# PG04__BALANCER.net
KiCad netlist of a schematic drawn in Altium Designer
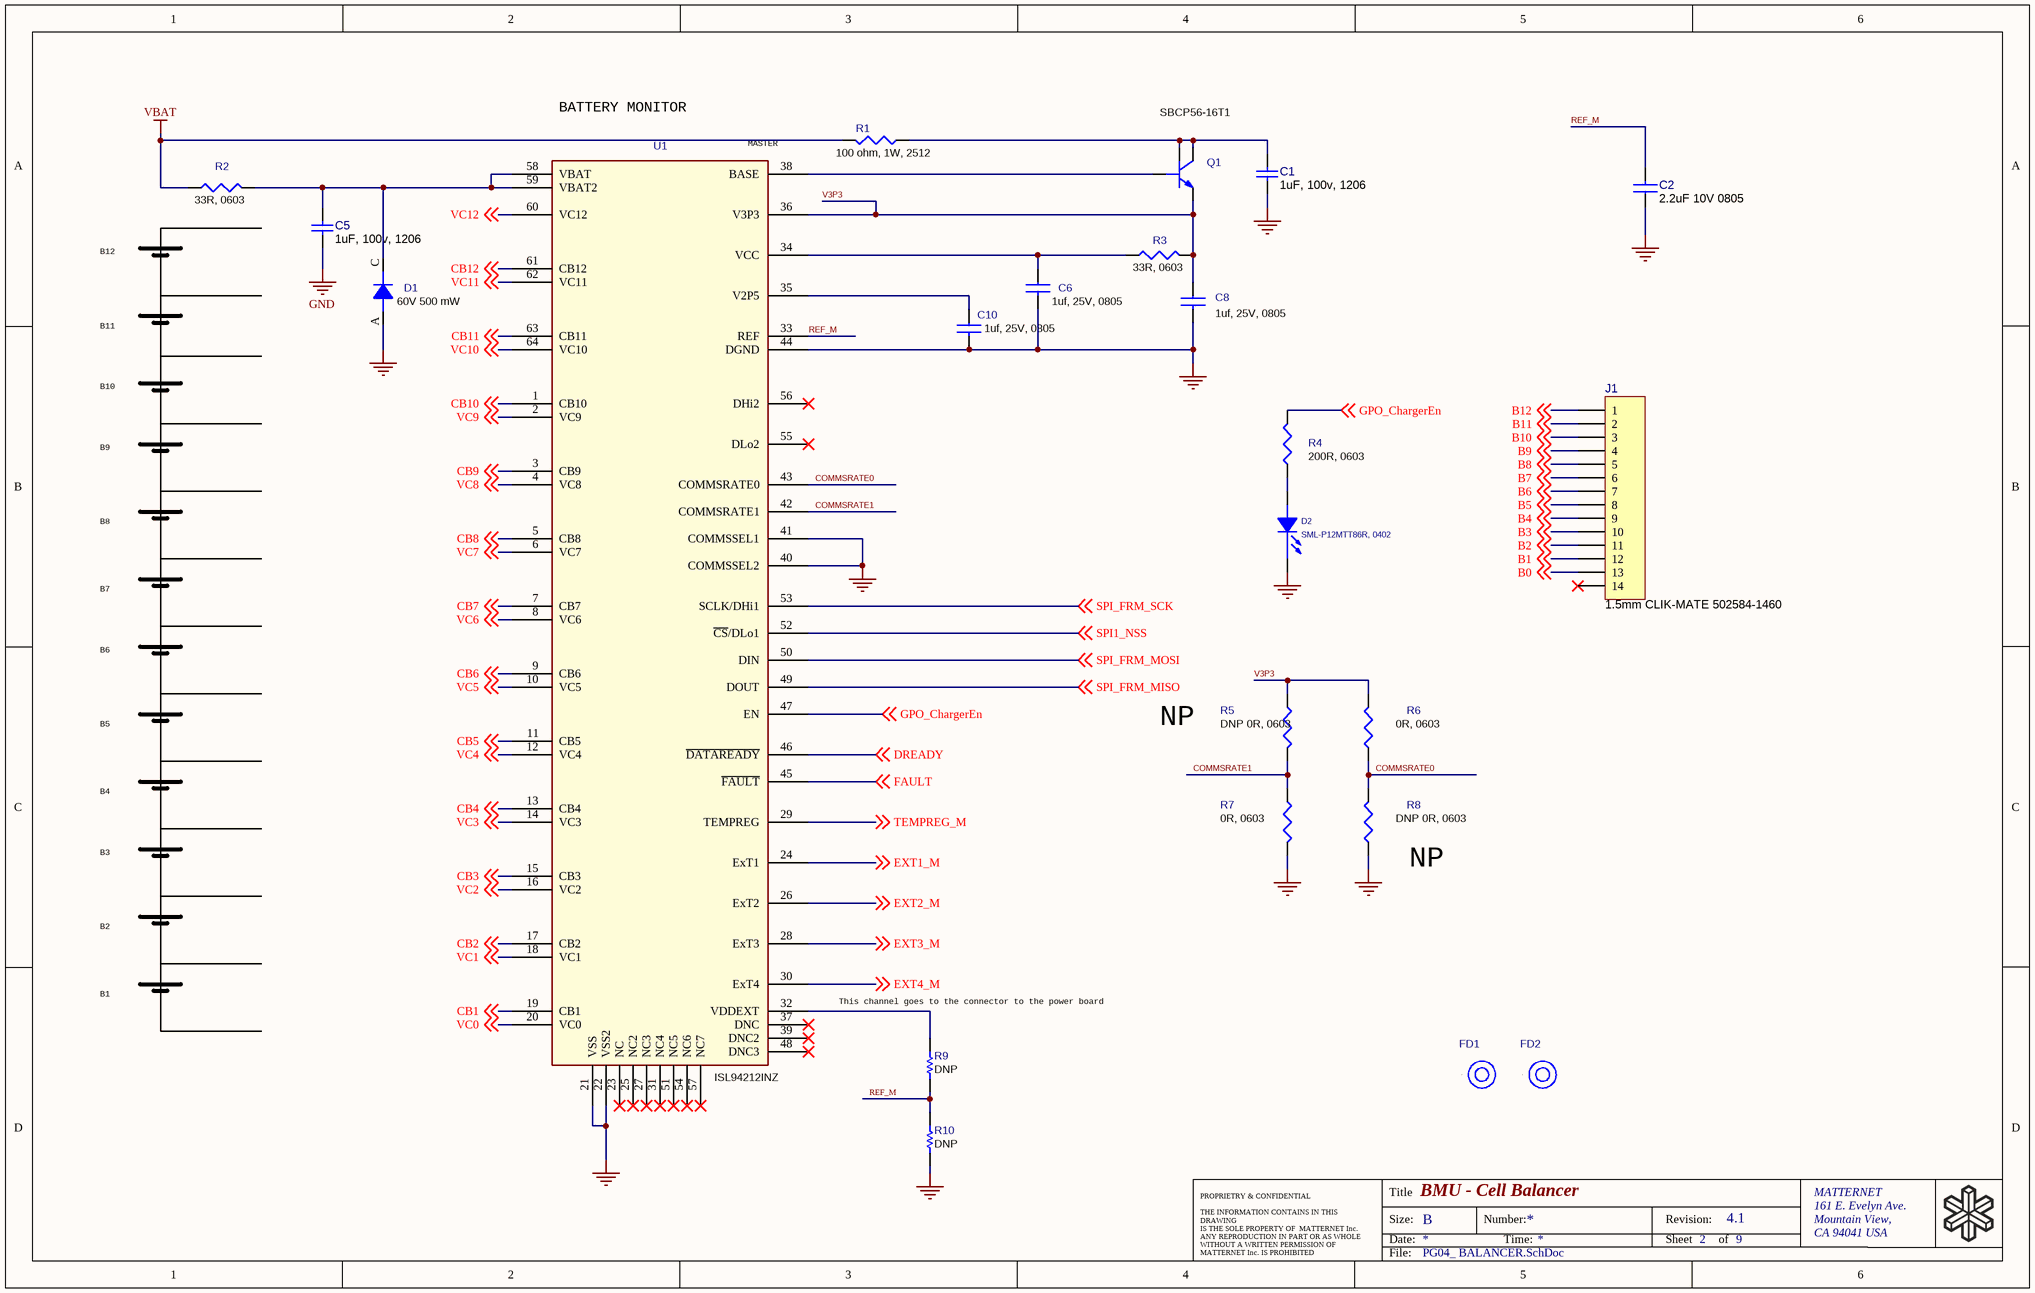
[diagram p0: PG04_ BALANCER.SchDoc]

(export (version "E")
  (design (tool "Eeschema 10.0.6"))
  (components
    (comp (ref "C1")
      (value "1uF, 100v, 1206")
      (footprint "C1206")
      (description "CAP CER 1UF 100V X7R 1210 AUTO F")
      (fields
        (field (name "MANUFACTURER") "KEMET")
        (field (name "MANUFACTURER PART NUMBER") "C1210X105K1RACAUTO")
      )
      (libsource (lib "Miscellaneous Devices") (part "Cap"))
    )
    (comp (ref "C2")
      (value "2.2uF 10V 0805")
      (footprint "C0805")
      (description "CAP CER 2.2UF 10V 10% X7R 0805")
      (fields
        (field (name "MANUFACTURER") "KEMET")
        (field (name "MANUFACTURER PART NUMBER") "C0805X225K8RACAUTO")
      )
      (libsource (lib "*") (part "CAP-Generic-0805"))
    )
    (comp (ref "C5")
      (value "1uF, 100v, 1206")
      (footprint "C1206")
      (description "CAP CER 1UF 100V X7R 1210 AUTO F")
      (fields
        (field (name "MANUFACTURER") "KEMET")
        (field (name "MANUFACTURER PART NUMBER") "C1210X105K1RACAUTO")
      )
      (libsource (lib "Miscellaneous Devices") (part "Cap"))
    )
    (comp (ref "C6")
      (value "1uf, 25V, 0805")
      (footprint "C0805")
      (description "CAP CER 1UF 25V X7R 0805")
      (fields
        (field (name "MANUFACTURER") "Murata")
        (field (name "MANUFACTURER PART NUMBER") "GCJ21BR71E105KA12L")
      )
      (libsource (lib "*") (part "CAP-Generic-0402"))
    )
    (comp (ref "C8")
      (value "1uf, 25V, 0805")
      (footprint "C0805")
      (description "CAP CER 1UF 25V X7R 0805")
      (fields
        (field (name "MANUFACTURER") "Murata")
        (field (name "MANUFACTURER PART NUMBER") "GCJ21BR71E105KA12L")
      )
      (libsource (lib "*") (part "CAP-Generic-0402"))
    )
    (comp (ref "C10")
      (value "1uf, 25V, 0805")
      (footprint "C0805")
      (description "CAP CER 1UF 25V X7R 0805")
      (fields
        (field (name "MANUFACTURER") "Murata")
        (field (name "MANUFACTURER PART NUMBER") "GCJ21BR71E105KA12L")
      )
      (libsource (lib "*") (part "CAP-Generic-0402"))
    )
    (comp (ref "D1")
      (value "60V 500 mW")
      (footprint "SOD-123")
      (description "DIODE ZENER 60V 500MW SOD123")
      (fields
        (field (name "MANUFACTURER") "ON Semiconductor")
        (field (name "MANUFACTURER PART NUMBER") "MMSZ5264BT1G")
      )
      (libsource (lib "*") (part "DIO-GENERIC"))
    )
    (comp (ref "D2")
      (value "SML-P12MTT86R, 0402")
      (footprint "D0402")
      (libsource (lib "M2_V8_BMU_V1.0") (part "LED-GENERIC"))
    )
    (comp (ref "FD1")
      (value "FIDUCIAL_REF")
      (footprint "FIDUCIAL_REFDES")
      (libsource (lib "*") (part "FIDUCIAL_REF"))
    )
    (comp (ref "FD2")
      (value "FIDUCIAL_REF")
      (footprint "FIDUCIAL_REFDES")
      (libsource (lib "*") (part "FIDUCIAL_REF"))
    )
    (comp (ref "J1")
      (value "1.5mm CLIK-MATE 502584-1460")
      (footprint "CONN14_1p5mm_SM")
      (description "CONN RCPT 14POS 0.059 TIN SMD")
      (fields (field (name "MANUFACTURER") "Molex") (field (name "MANUFACTURER PART NUMBER") "502584-1460"))
      (libsource (lib "Miscellaneous Connectors") (part "Header 14"))
    )
    (comp (ref "Q1")
      (value "SBCP56-16T1")
      (footprint "SOT-223")
      (description "TRANS NPN 80V 1.0A SOT-223")
      (fields
        (field (name "MANUFACTURER") "ON Semiconductor")
        (field (name "MANUFACTURER PART NUMBER") "SBCP56-16T1G")
      )
      (libsource (lib "*") (part "Trans-Generic_2"))
    )
    (comp (ref "R1")
      (value "100 ohm, 1W, 2512")
      (footprint "2512")
      (description "RES SMD 100 OHM 5% 1W 2512")
      (fields
        (field (name "MANUFACTURER") "Panasonic")
        (field (name "MANUFACTURER PART NUMBER") "ERJ-1TYJ101U")
      )
      (libsource (lib "*") (part "R-Generic"))
    )
    (comp (ref "R2")
      (value "33R, 0603")
      (footprint "R0603")
      (description "RES SMD 33 OHM 1% 1/10W 0603")
      (fields
        (field (name "MANUFACTURER") "Yageo")
        (field (name "MANUFACTURER PART NUMBER") "AC0603FR-0733RL")
      )
      (libsource (lib "*") (part "R-Generic-0603"))
    )
    (comp (ref "R3")
      (value "33R, 0603")
      (footprint "R0603")
      (description "RES SMD 33 OHM 1% 1/10W 0603")
      (fields
        (field (name "MANUFACTURER") "Yageo")
        (field (name "MANUFACTURER PART NUMBER") "AC0603FR-0733RL")
      )
      (libsource (lib "*") (part "R-Generic-0603"))
    )
    (comp (ref "R4")
      (value "200R, 0603")
      (footprint "R0603")
      (description "RES SMD 200 OHM 1% 1/10W 0603")
      (fields
        (field (name "MANUFACTURER") "Yageo")
        (field (name "MANUFACTURER PART NUMBER") "AC0603FR-07200RL")
      )
      (libsource (lib "*") (part "R-Generic-0603"))
    )
    (comp (ref "R5")
      (value "DNP 0R, 0603")
      (footprint "R0603")
      (description "DNP")
      (libsource (lib "*") (part "R-Generic-0402"))
    )
    (comp (ref "R6")
      (value "0R, 0603")
      (footprint "R0603")
      (description "RES SMD 0 OHM JUMPER 1/10W 0603")
      (fields
        (field (name "MANUFACTURER") "Yageo")
        (field (name "MANUFACTURER PART NUMBER") "RC0603FR-070RL")
      )
      (libsource (lib "*") (part "R-Generic-0402"))
    )
    (comp (ref "R7")
      (value "0R, 0603")
      (footprint "R0603")
      (description "RES SMD 0 OHM JUMPER 1/10W 0603")
      (fields
        (field (name "MANUFACTURER") "Yageo")
        (field (name "MANUFACTURER PART NUMBER") "RC0603FR-070RL")
      )
      (libsource (lib "*") (part "R-Generic-0402"))
    )
    (comp (ref "R8")
      (value "DNP 0R, 0603")
      (footprint "R0603")
      (description "DNP")
      (libsource (lib "*") (part "R-Generic-0402"))
    )
    (comp (ref "R9")
      (value "DNP")
      (footprint "R0402")
      (description "Resistor")
      (fields (field (name "PUBLISHER") "Altium Limited"))
      (libsource (lib "Miscellaneous Devices") (part "Res1"))
    )
    (comp (ref "R10")
      (value "DNP")
      (footprint "R0402")
      (description "Resistor")
      (fields (field (name "PUBLISHER") "Altium Limited"))
      (libsource (lib "Miscellaneous Devices") (part "Res1"))
    )
    (comp (ref "U1")
      (value "ISL94212INZ")
      (footprint "TQFP-64")
      (description "Battery Management Multi-Cell Li-Ion Battery Manager")
      (fields (field (name "MANUFACTURER") "Renesas"))
      (libsource (lib "M2_V8_BMU_V1.0") (part "BATTMAN-ISL94212INZ-700-498"))
    )
  )
  (nets
    (net (code "1") (name "/COMMSRATE0") (class "Default")
      (node (ref "R6") (pin "2") (pinfunction "2_2") (pintype "passive"))
      (node (ref "R8") (pin "1") (pinfunction "1_1") (pintype "passive"))
      (node (ref "U1") (pin "43") (pinfunction "COMMSRATE0_43") (pintype "passive"))
    )
    (net (code "2") (name "/COMMSRATE1") (class "Default")
      (node (ref "R5") (pin "2") (pinfunction "2_2") (pintype "passive"))
      (node (ref "R7") (pin "1") (pinfunction "1_1") (pintype "passive"))
      (node (ref "U1") (pin "42") (pinfunction "COMMSRATE1_42") (pintype "passive"))
    )
    (net (code "3") (name "/REF_M") (class "Default")
      (node (ref "C2") (pin "2") (pinfunction "2_2") (pintype "passive"))
      (node (ref "R10") (pin "2") (pinfunction "2_2") (pintype "passive"))
      (node (ref "R9") (pin "1") (pinfunction "1_1") (pintype "passive"))
      (node (ref "U1") (pin "33") (pinfunction "REF_33") (pintype "passive"))
    )
    (net (code "4") (name "/V3P3") (class "Default")
      (node (ref "C8") (pin "1") (pinfunction "1_1") (pintype "passive"))
      (node (ref "Q1") (pin "3") (pinfunction "E_3") (pintype "passive"))
      (node (ref "R3") (pin "2") (pinfunction "2_2") (pintype "passive"))
      (node (ref "R5") (pin "1") (pinfunction "1_1") (pintype "passive"))
      (node (ref "R6") (pin "1") (pinfunction "1_1") (pintype "passive"))
      (node (ref "U1") (pin "36") (pinfunction "V3P3_36") (pintype "passive"))
    )
    (net (code "5") (name "B0") (class "Default")
      (node (ref "J1") (pin "13") (pinfunction "13_13") (pintype "passive"))
    )
    (net (code "6") (name "B1") (class "Default")
      (node (ref "J1") (pin "12") (pinfunction "12_12") (pintype "passive"))
    )
    (net (code "7") (name "B2") (class "Default")
      (node (ref "J1") (pin "11") (pinfunction "11_11") (pintype "passive"))
    )
    (net (code "8") (name "B3") (class "Default")
      (node (ref "J1") (pin "10") (pinfunction "10_10") (pintype "passive"))
    )
    (net (code "9") (name "B4") (class "Default")
      (node (ref "J1") (pin "9") (pinfunction "9_9") (pintype "passive"))
    )
    (net (code "10") (name "B5") (class "Default")
      (node (ref "J1") (pin "8") (pinfunction "8_8") (pintype "passive"))
    )
    (net (code "11") (name "B6") (class "Default")
      (node (ref "J1") (pin "7") (pinfunction "7_7") (pintype "passive"))
    )
    (net (code "12") (name "B7") (class "Default")
      (node (ref "J1") (pin "6") (pinfunction "6_6") (pintype "passive"))
    )
    (net (code "13") (name "B8") (class "Default")
      (node (ref "J1") (pin "5") (pinfunction "5_5") (pintype "passive"))
    )
    (net (code "14") (name "B9") (class "Default")
      (node (ref "J1") (pin "4") (pinfunction "4_4") (pintype "passive"))
    )
    (net (code "15") (name "B10") (class "Default")
      (node (ref "J1") (pin "3") (pinfunction "3_3") (pintype "passive"))
    )
    (net (code "16") (name "B11") (class "Default")
      (node (ref "J1") (pin "2") (pinfunction "2_2") (pintype "passive"))
    )
    (net (code "17") (name "B12") (class "Default")
      (node (ref "J1") (pin "1") (pinfunction "1_1") (pintype "passive"))
    )
    (net (code "18") (name "CB1") (class "Default")
      (node (ref "U1") (pin "19") (pinfunction "CB1_19") (pintype "passive"))
    )
    (net (code "19") (name "CB2") (class "Default")
      (node (ref "U1") (pin "17") (pinfunction "CB2_17") (pintype "passive"))
    )
    (net (code "20") (name "CB3") (class "Default")
      (node (ref "U1") (pin "15") (pinfunction "CB3_15") (pintype "passive"))
    )
    (net (code "21") (name "CB4") (class "Default")
      (node (ref "U1") (pin "13") (pinfunction "CB4_13") (pintype "passive"))
    )
    (net (code "22") (name "CB5") (class "Default")
      (node (ref "U1") (pin "11") (pinfunction "CB5_11") (pintype "passive"))
    )
    (net (code "23") (name "CB6") (class "Default")
      (node (ref "U1") (pin "9") (pinfunction "CB6_9") (pintype "passive"))
    )
    (net (code "24") (name "CB7") (class "Default")
      (node (ref "U1") (pin "7") (pinfunction "CB7_7") (pintype "passive"))
    )
    (net (code "25") (name "CB8") (class "Default")
      (node (ref "U1") (pin "5") (pinfunction "CB8_5") (pintype "passive"))
    )
    (net (code "26") (name "CB9") (class "Default")
      (node (ref "U1") (pin "3") (pinfunction "CB9_3") (pintype "passive"))
    )
    (net (code "27") (name "CB10") (class "Default")
      (node (ref "U1") (pin "1") (pinfunction "CB10_1") (pintype "passive"))
    )
    (net (code "28") (name "CB11") (class "Default")
      (node (ref "U1") (pin "63") (pinfunction "CB11_63") (pintype "passive"))
    )
    (net (code "29") (name "CB12") (class "Default")
      (node (ref "U1") (pin "61") (pinfunction "CB12_61") (pintype "passive"))
    )
    (net (code "30") (name "DREADY") (class "Default")
      (node (ref "U1") (pin "46") (pinfunction "~{DATAREADY}_46") (pintype "passive"))
    )
    (net (code "31") (name "EXT1_M") (class "Default")
      (node (ref "U1") (pin "24") (pinfunction "ExT1_24") (pintype "passive"))
    )
    (net (code "32") (name "EXT2_M") (class "Default")
      (node (ref "U1") (pin "26") (pinfunction "ExT2_26") (pintype "passive"))
    )
    (net (code "33") (name "EXT3_M") (class "Default")
      (node (ref "U1") (pin "28") (pinfunction "ExT3_28") (pintype "passive"))
    )
    (net (code "34") (name "EXT4_M") (class "Default")
      (node (ref "U1") (pin "30") (pinfunction "ExT4_30") (pintype "passive"))
    )
    (net (code "35") (name "FAULT") (class "Default")
      (node (ref "U1") (pin "45") (pinfunction "~{FAULT}_45") (pintype "passive"))
    )
    (net (code "36") (name "GND") (class "Default")
      (node (ref "C1") (pin "2") (pinfunction "2_2") (pintype "passive"))
      (node (ref "C10") (pin "2") (pinfunction "2_2") (pintype "passive"))
      (node (ref "C2") (pin "1") (pinfunction "1_1") (pintype "passive"))
      (node (ref "C5") (pin "1") (pinfunction "1_1") (pintype "passive"))
      (node (ref "C6") (pin "2") (pinfunction "2_2") (pintype "passive"))
      (node (ref "C8") (pin "2") (pinfunction "2_2") (pintype "passive"))
      (node (ref "D1") (pin "A") (pinfunction "ANODE_A") (pintype "passive"))
      (node (ref "D2") (pin "C") (pinfunction "CATHODE_C") (pintype "passive"))
      (node (ref "R10") (pin "1") (pinfunction "1_1") (pintype "passive"))
      (node (ref "R7") (pin "2") (pinfunction "2_2") (pintype "passive"))
      (node (ref "R8") (pin "2") (pinfunction "2_2") (pintype "passive"))
      (node (ref "U1") (pin "21") (pinfunction "VSS_21") (pintype "passive"))
      (node (ref "U1") (pin "22") (pinfunction "VSS2_22") (pintype "passive"))
      (node (ref "U1") (pin "40") (pinfunction "COMMSSEL2_40") (pintype "passive"))
      (node (ref "U1") (pin "41") (pinfunction "COMMSSEL1_41") (pintype "passive"))
      (node (ref "U1") (pin "44") (pinfunction "DGND_44") (pintype "passive"))
    )
    (net (code "37") (name "GPO_ChargerEn") (class "Default")
      (node (ref "R4") (pin "2") (pinfunction "2_2") (pintype "passive"))
      (node (ref "U1") (pin "47") (pinfunction "EN_47") (pintype "passive"))
    )
    (net (code "38") (name "Net-(C1-Pad1)") (class "Default")
      (node (ref "C1") (pin "1") (pinfunction "1_1") (pintype "passive"))
      (node (ref "Q1") (pin "2") (pinfunction "C_2") (pintype "power_in"))
      (node (ref "Q1") (pin "4") (pinfunction "C_4") (pintype "power_in"))
      (node (ref "R1") (pin "1") (pinfunction "1_1") (pintype "passive"))
    )
    (net (code "39") (name "Net-(D1-CATHODE)") (class "Default")
      (node (ref "C5") (pin "2") (pinfunction "2_2") (pintype "passive"))
      (node (ref "D1") (pin "C") (pinfunction "CATHODE_C") (pintype "passive"))
      (node (ref "R2") (pin "2") (pinfunction "2_2") (pintype "passive"))
      (node (ref "U1") (pin "58") (pinfunction "VBAT_58") (pintype "passive"))
      (node (ref "U1") (pin "59") (pinfunction "VBAT2_59") (pintype "passive"))
    )
    (net (code "40") (name "Net-(D2-ANODE)") (class "Default")
      (node (ref "D2") (pin "A") (pinfunction "ANODE_A") (pintype "passive"))
      (node (ref "R4") (pin "1") (pinfunction "1_1") (pintype "passive"))
    )
    (net (code "41") (name "Net-(Q1-B)") (class "Default")
      (node (ref "Q1") (pin "1") (pinfunction "B_1") (pintype "passive"))
      (node (ref "U1") (pin "38") (pinfunction "BASE_38") (pintype "passive"))
    )
    (net (code "42") (name "Net-(U1-V2P5)") (class "Default")
      (node (ref "C10") (pin "1") (pinfunction "1_1") (pintype "passive"))
      (node (ref "U1") (pin "35") (pinfunction "V2P5_35") (pintype "passive"))
    )
    (net (code "43") (name "Net-(U1-VCC)") (class "Default")
      (node (ref "C6") (pin "1") (pinfunction "1_1") (pintype "passive"))
      (node (ref "R3") (pin "1") (pinfunction "1_1") (pintype "passive"))
      (node (ref "U1") (pin "34") (pinfunction "VCC_34") (pintype "passive"))
    )
    (net (code "44") (name "Net-(U1-VDDEXT)") (class "Default")
      (node (ref "R9") (pin "2") (pinfunction "2_2") (pintype "passive"))
      (node (ref "U1") (pin "32") (pinfunction "VDDEXT_32") (pintype "passive"))
    )
    (net (code "45") (name "SPI1_NSS") (class "Default")
      (node (ref "U1") (pin "52") (pinfunction "~{CS}/DLo1_52") (pintype "passive"))
    )
    (net (code "46") (name "SPI_FRM_MISO") (class "Default")
      (node (ref "U1") (pin "49") (pinfunction "DOUT_49") (pintype "passive"))
    )
    (net (code "47") (name "SPI_FRM_MOSI") (class "Default")
      (node (ref "U1") (pin "50") (pinfunction "DIN_50") (pintype "passive"))
    )
    (net (code "48") (name "SPI_FRM_SCK") (class "Default")
      (node (ref "U1") (pin "53") (pinfunction "SCLK/DHi1_53") (pintype "passive"))
    )
    (net (code "49") (name "TEMPREG_M") (class "Default")
      (node (ref "U1") (pin "29") (pinfunction "TEMPREG_29") (pintype "passive"))
    )
    (net (code "50") (name "VBAT") (class "Default")
      (node (ref "R1") (pin "2") (pinfunction "2_2") (pintype "passive"))
      (node (ref "R2") (pin "1") (pinfunction "1_1") (pintype "passive"))
    )
    (net (code "51") (name "VC0") (class "Default")
      (node (ref "U1") (pin "20") (pinfunction "VC0_20") (pintype "passive"))
    )
    (net (code "52") (name "VC1") (class "Default")
      (node (ref "U1") (pin "18") (pinfunction "VC1_18") (pintype "passive"))
    )
    (net (code "53") (name "VC2") (class "Default")
      (node (ref "U1") (pin "16") (pinfunction "VC2_16") (pintype "passive"))
    )
    (net (code "54") (name "VC3") (class "Default")
      (node (ref "U1") (pin "14") (pinfunction "VC3_14") (pintype "passive"))
    )
    (net (code "55") (name "VC4") (class "Default")
      (node (ref "U1") (pin "12") (pinfunction "VC4_12") (pintype "passive"))
    )
    (net (code "56") (name "VC5") (class "Default")
      (node (ref "U1") (pin "10") (pinfunction "VC5_10") (pintype "passive"))
    )
    (net (code "57") (name "VC6") (class "Default")
      (node (ref "U1") (pin "8") (pinfunction "VC6_8") (pintype "passive"))
    )
    (net (code "58") (name "VC7") (class "Default")
      (node (ref "U1") (pin "6") (pinfunction "VC7_6") (pintype "passive"))
    )
    (net (code "59") (name "VC8") (class "Default")
      (node (ref "U1") (pin "4") (pinfunction "VC8_4") (pintype "passive"))
    )
    (net (code "60") (name "VC9") (class "Default")
      (node (ref "U1") (pin "2") (pinfunction "VC9_2") (pintype "passive"))
    )
    (net (code "61") (name "VC10") (class "Default")
      (node (ref "U1") (pin "64") (pinfunction "VC10_64") (pintype "passive"))
    )
    (net (code "62") (name "VC11") (class "Default")
      (node (ref "U1") (pin "62") (pinfunction "VC11_62") (pintype "passive"))
    )
    (net (code "63") (name "VC12") (class "Default")
      (node (ref "U1") (pin "60") (pinfunction "VC12_60") (pintype "passive"))
    )
    (net (code "64") (name "unconnected-(FD1-Pad1)") (class "Default")
      (node (ref "FD1") (pin "1") (pinfunction "1_1") (pintype "passive"))
    )
    (net (code "65") (name "unconnected-(FD2-Pad1)") (class "Default")
      (node (ref "FD2") (pin "1") (pinfunction "1_1") (pintype "passive"))
    )
    (net (code "66") (name "unconnected-(J1-Pad14)") (class "Default")
      (node (ref "J1") (pin "14") (pinfunction "14_14") (pintype "passive+no_connect"))
    )
    (net (code "67") (name "unconnected-(U1-DHi2-Pad56)") (class "Default")
      (node (ref "U1") (pin "56") (pinfunction "DHi2_56") (pintype "passive+no_connect"))
    )
    (net (code "68") (name "unconnected-(U1-DLo2-Pad55)") (class "Default")
      (node (ref "U1") (pin "55") (pinfunction "DLo2_55") (pintype "passive+no_connect"))
    )
    (net (code "69") (name "unconnected-(U1-DNC-Pad37)") (class "Default")
      (node (ref "U1") (pin "37") (pinfunction "DNC_37") (pintype "passive+no_connect"))
    )
    (net (code "70") (name "unconnected-(U1-DNC2-Pad39)") (class "Default")
      (node (ref "U1") (pin "39") (pinfunction "DNC2_39") (pintype "passive+no_connect"))
    )
    (net (code "71") (name "unconnected-(U1-DNC3-Pad48)") (class "Default")
      (node (ref "U1") (pin "48") (pinfunction "DNC3_48") (pintype "passive+no_connect"))
    )
    (net (code "72") (name "unconnected-(U1-NC-Pad23)") (class "Default")
      (node (ref "U1") (pin "23") (pinfunction "NC_23") (pintype "passive+no_connect"))
    )
    (net (code "73") (name "unconnected-(U1-NC2-Pad25)") (class "Default")
      (node (ref "U1") (pin "25") (pinfunction "NC2_25") (pintype "passive+no_connect"))
    )
    (net (code "74") (name "unconnected-(U1-NC3-Pad27)") (class "Default")
      (node (ref "U1") (pin "27") (pinfunction "NC3_27") (pintype "passive+no_connect"))
    )
    (net (code "75") (name "unconnected-(U1-NC4-Pad31)") (class "Default")
      (node (ref "U1") (pin "31") (pinfunction "NC4_31") (pintype "passive+no_connect"))
    )
    (net (code "76") (name "unconnected-(U1-NC5-Pad51)") (class "Default")
      (node (ref "U1") (pin "51") (pinfunction "NC5_51") (pintype "passive+no_connect"))
    )
    (net (code "77") (name "unconnected-(U1-NC6-Pad54)") (class "Default")
      (node (ref "U1") (pin "54") (pinfunction "NC6_54") (pintype "passive+no_connect"))
    )
    (net (code "78") (name "unconnected-(U1-NC7-Pad57)") (class "Default")
      (node (ref "U1") (pin "57") (pinfunction "NC7_57") (pintype "passive+no_connect"))
    )
  )
)
